# HW2_1.net
KiCad netlist of a schematic drawn in EAGLE
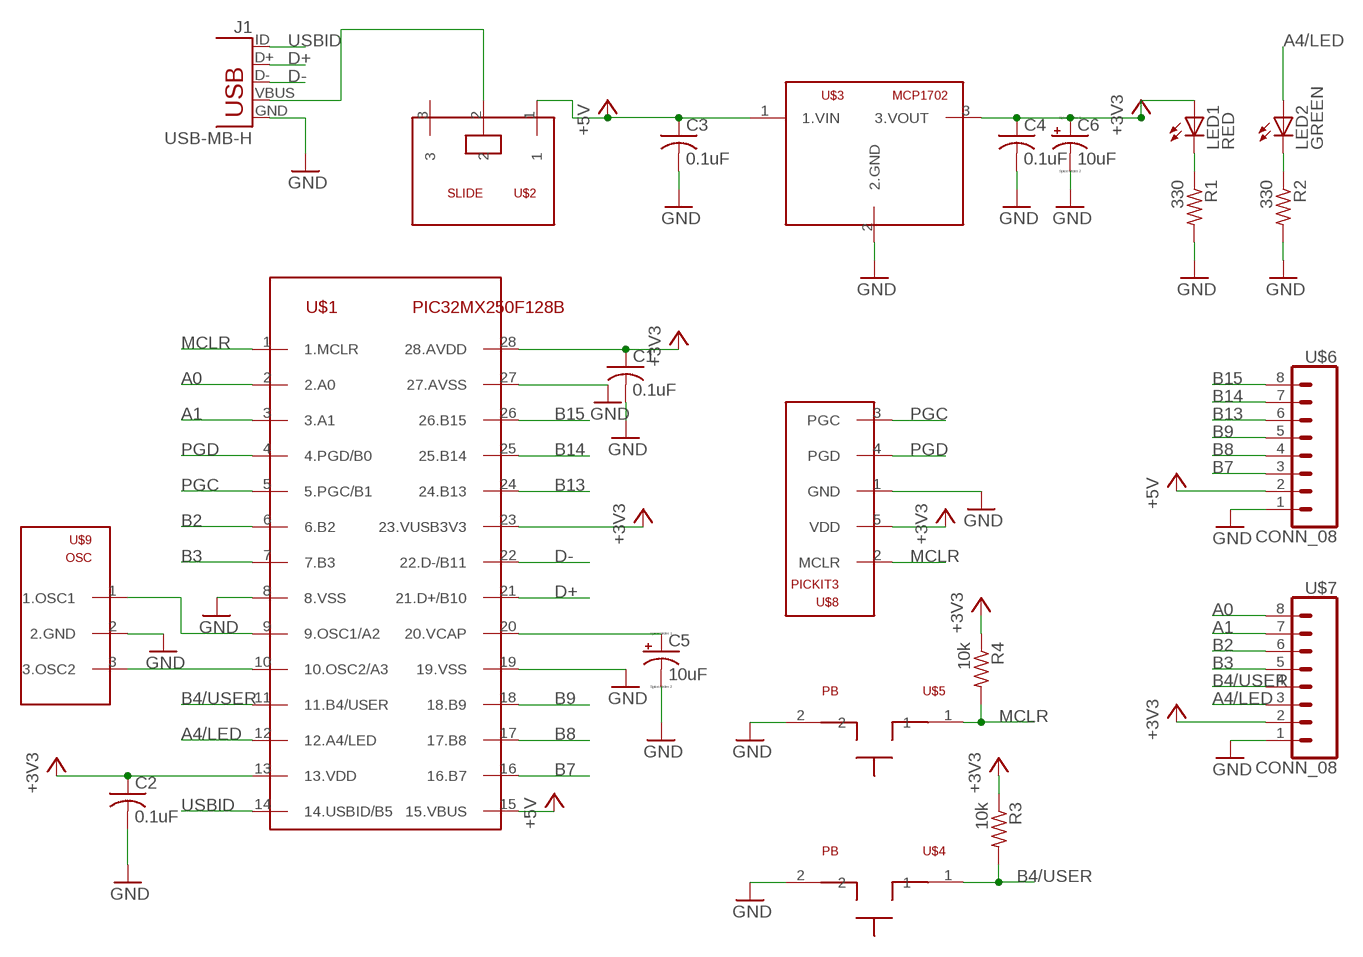
[diagram p0: schematic, sheet 1]

(export (version "E")
  (design (tool "Eeschema 10.0.6"))
  (components
    (comp (ref "C1")
      (value "0.1uF")
      (footprint "eagle-import:C025-025X050")
      (libsource (lib "eagle-import") (part "C-US025-025X050"))
    )
    (comp (ref "C2")
      (value "0.1uF")
      (footprint "eagle-import:C025-025X050")
      (libsource (lib "eagle-import") (part "C-US025-025X050"))
    )
    (comp (ref "C3")
      (value "0.1uF")
      (footprint "eagle-import:C025-025X050")
      (libsource (lib "eagle-import") (part "C-US025-025X050"))
    )
    (comp (ref "C4")
      (value "0.1uF")
      (footprint "eagle-import:C025-025X050")
      (libsource (lib "eagle-import") (part "C-US025-025X050"))
    )
    (comp (ref "C5")
      (value "10uF")
      (footprint "eagle-import:B45181B")
      (libsource (lib "eagle-import") (part "CPOL-USB45181B"))
    )
    (comp (ref "C6")
      (value "10uF")
      (footprint "eagle-import:B45181B")
      (libsource (lib "eagle-import") (part "CPOL-USB45181B"))
    )
    (comp (ref "J1")
      (value "USB-MB-H")
      (footprint "eagle-import:USB-MB-H")
      (libsource (lib "eagle-import") (part "USB-MB-H"))
    )
    (comp (ref "LED1")
      (value "RED")
      (footprint "eagle-import:LED3MM")
      (libsource (lib "eagle-import") (part "LED3MM"))
    )
    (comp (ref "LED2")
      (value "GREEN")
      (footprint "eagle-import:LED3MM")
      (libsource (lib "eagle-import") (part "LED3MM"))
    )
    (comp (ref "R1")
      (value "330")
      (footprint "eagle-import:0207_7")
      (libsource (lib "eagle-import") (part "R-US_0207/7"))
    )
    (comp (ref "R2")
      (value "330")
      (footprint "eagle-import:0207_7")
      (libsource (lib "eagle-import") (part "R-US_0207/7"))
    )
    (comp (ref "R3")
      (value "10k")
      (footprint "eagle-import:0207_7")
      (libsource (lib "eagle-import") (part "R-US_0207/7"))
    )
    (comp (ref "R4")
      (value "10k")
      (footprint "eagle-import:0207_7")
      (libsource (lib "eagle-import") (part "R-US_0207/7"))
    )
    (comp (ref "U$1")
      (value "PIC32MX250F128B")
      (footprint "eagle-import:DIL28-3")
      (libsource (lib "eagle-import") (part "PIC32MX250F128B"))
    )
    (comp (ref "U$2")
      (value "SLIDE")
      (footprint "eagle-import:SLIDE")
      (libsource (lib "eagle-import") (part "SLIDE"))
    )
    (comp (ref "U$3")
      (value "MCP1702")
      (footprint "eagle-import:TO92")
      (libsource (lib "eagle-import") (part "MCP1702"))
    )
    (comp (ref "U$4") (value "PB") (footprint "eagle-import:PB") (libsource (lib "eagle-import") (part "PB")))
    (comp (ref "U$5") (value "PB") (footprint "eagle-import:PB") (libsource (lib "eagle-import") (part "PB")))
    (comp (ref "U$6")
      (value "CONN_08")
      (footprint "eagle-import:1X08")
      (libsource (lib "eagle-import") (part "CONN_08"))
    )
    (comp (ref "U$7")
      (value "CONN_08")
      (footprint "eagle-import:1X08")
      (libsource (lib "eagle-import") (part "CONN_08"))
    )
    (comp (ref "U$8")
      (value "PICKIT3")
      (footprint "eagle-import:1X05")
      (libsource (lib "eagle-import") (part "PICKIT3"))
    )
    (comp (ref "U$9")
      (value "OSC")
      (footprint "eagle-import:OSC")
      (libsource (lib "eagle-import") (part "OSC"))
    )
  )
  (nets
    (net (code "1") (name "+3V3") (class "Default")
      (node (ref "C1") (pin "1") (pinfunction "1_1") (pintype "passive"))
      (node (ref "C2") (pin "1") (pinfunction "1_1") (pintype "passive"))
      (node (ref "C4") (pin "1") (pinfunction "1_1") (pintype "passive"))
      (node (ref "C6") (pin "+") (pinfunction "+_+") (pintype "passive"))
      (node (ref "LED1") (pin "A") (pinfunction "A_A") (pintype "passive"))
      (node (ref "R3") (pin "1") (pinfunction "1_1") (pintype "passive"))
      (node (ref "R4") (pin "1") (pinfunction "1_1") (pintype "passive"))
      (node (ref "U$1") (pin "13") (pinfunction "13.VDD_13") (pintype "bidirectional"))
      (node (ref "U$1") (pin "23") (pinfunction "23.VUSB3V3_23") (pintype "bidirectional"))
      (node (ref "U$1") (pin "28") (pinfunction "28.AVDD_28") (pintype "bidirectional"))
      (node (ref "U$3") (pin "3") (pinfunction "3.VOUT_3") (pintype "bidirectional"))
      (node (ref "U$7") (pin "2") (pinfunction "2_2") (pintype "passive"))
      (node (ref "U$8") (pin "5") (pinfunction "VDD_5") (pintype "bidirectional"))
    )
    (net (code "2") (name "+5V") (class "Default")
      (node (ref "C3") (pin "1") (pinfunction "1_1") (pintype "passive"))
      (node (ref "U$1") (pin "15") (pinfunction "15.VBUS_15") (pintype "bidirectional"))
      (node (ref "U$2") (pin "1") (pinfunction "1_1") (pintype "bidirectional"))
      (node (ref "U$3") (pin "1") (pinfunction "1.VIN_1") (pintype "bidirectional"))
      (node (ref "U$6") (pin "2") (pinfunction "2_2") (pintype "passive"))
    )
    (net (code "3") (name "/A0") (class "Default")
      (node (ref "U$1") (pin "2") (pinfunction "2.A0_2") (pintype "bidirectional"))
      (node (ref "U$7") (pin "8") (pinfunction "8_8") (pintype "passive"))
    )
    (net (code "4") (name "/A1") (class "Default")
      (node (ref "U$1") (pin "3") (pinfunction "3.A1_3") (pintype "bidirectional"))
      (node (ref "U$7") (pin "7") (pinfunction "7_7") (pintype "passive"))
    )
    (net (code "5") (name "/A4{slash}LED") (class "Default")
      (node (ref "LED2") (pin "A") (pinfunction "A_A") (pintype "passive"))
      (node (ref "U$1") (pin "12") (pinfunction "12.A4/LED_12") (pintype "bidirectional"))
      (node (ref "U$7") (pin "3") (pinfunction "3_3") (pintype "passive"))
    )
    (net (code "6") (name "/B2") (class "Default")
      (node (ref "U$1") (pin "6") (pinfunction "6.B2_6") (pintype "bidirectional"))
      (node (ref "U$7") (pin "6") (pinfunction "6_6") (pintype "passive"))
    )
    (net (code "7") (name "/B3") (class "Default")
      (node (ref "U$1") (pin "7") (pinfunction "7.B3_7") (pintype "bidirectional"))
      (node (ref "U$7") (pin "5") (pinfunction "5_5") (pintype "passive"))
    )
    (net (code "8") (name "/B4{slash}USER") (class "Default")
      (node (ref "R3") (pin "2") (pinfunction "2_2") (pintype "passive"))
      (node (ref "U$1") (pin "11") (pinfunction "11.B4/USER_11") (pintype "bidirectional"))
      (node (ref "U$4") (pin "1") (pinfunction "1_1") (pintype "bidirectional"))
      (node (ref "U$7") (pin "4") (pinfunction "4_4") (pintype "passive"))
    )
    (net (code "9") (name "/B7") (class "Default")
      (node (ref "U$1") (pin "16") (pinfunction "16.B7_16") (pintype "bidirectional"))
      (node (ref "U$6") (pin "3") (pinfunction "3_3") (pintype "passive"))
    )
    (net (code "10") (name "/B8") (class "Default")
      (node (ref "U$1") (pin "17") (pinfunction "17.B8_17") (pintype "bidirectional"))
      (node (ref "U$6") (pin "4") (pinfunction "4_4") (pintype "passive"))
    )
    (net (code "11") (name "/B9") (class "Default")
      (node (ref "U$1") (pin "18") (pinfunction "18.B9_18") (pintype "bidirectional"))
      (node (ref "U$6") (pin "5") (pinfunction "5_5") (pintype "passive"))
    )
    (net (code "12") (name "/B13") (class "Default")
      (node (ref "U$1") (pin "24") (pinfunction "24.B13_24") (pintype "bidirectional"))
      (node (ref "U$6") (pin "6") (pinfunction "6_6") (pintype "passive"))
    )
    (net (code "13") (name "/B14") (class "Default")
      (node (ref "U$1") (pin "25") (pinfunction "25.B14_25") (pintype "bidirectional"))
      (node (ref "U$6") (pin "7") (pinfunction "7_7") (pintype "passive"))
    )
    (net (code "14") (name "/B15") (class "Default")
      (node (ref "U$1") (pin "26") (pinfunction "26.B15_26") (pintype "bidirectional"))
      (node (ref "U$6") (pin "8") (pinfunction "8_8") (pintype "passive"))
    )
    (net (code "15") (name "/D+") (class "Default")
      (node (ref "J1") (pin "D+") (pinfunction "D+_D+") (pintype "bidirectional"))
      (node (ref "U$1") (pin "21") (pinfunction "21.D+/B10_21") (pintype "bidirectional"))
    )
    (net (code "16") (name "/D-") (class "Default")
      (node (ref "J1") (pin "D-") (pinfunction "D-_D-") (pintype "bidirectional"))
      (node (ref "U$1") (pin "22") (pinfunction "22.D-/B11_22") (pintype "bidirectional"))
    )
    (net (code "17") (name "/MCLR") (class "Default")
      (node (ref "R4") (pin "2") (pinfunction "2_2") (pintype "passive"))
      (node (ref "U$1") (pin "1") (pinfunction "1.MCLR_1") (pintype "bidirectional"))
      (node (ref "U$5") (pin "1") (pinfunction "1_1") (pintype "bidirectional"))
      (node (ref "U$8") (pin "2") (pinfunction "MCLR_2") (pintype "bidirectional"))
    )
    (net (code "18") (name "/PGC") (class "Default")
      (node (ref "U$1") (pin "5") (pinfunction "5.PGC/B1_5") (pintype "bidirectional"))
      (node (ref "U$8") (pin "3") (pinfunction "PGC_3") (pintype "bidirectional"))
    )
    (net (code "19") (name "/PGD") (class "Default")
      (node (ref "U$1") (pin "4") (pinfunction "4.PGD/B0_4") (pintype "bidirectional"))
      (node (ref "U$8") (pin "4") (pinfunction "PGD_4") (pintype "bidirectional"))
    )
    (net (code "20") (name "/USBID") (class "Default")
      (node (ref "J1") (pin "ID") (pinfunction "ID_ID") (pintype "bidirectional"))
      (node (ref "U$1") (pin "14") (pinfunction "14.USBID/B5_14") (pintype "bidirectional"))
    )
    (net (code "21") (name "GND") (class "Default")
      (node (ref "C1") (pin "2") (pinfunction "2_2") (pintype "passive"))
      (node (ref "C2") (pin "2") (pinfunction "2_2") (pintype "passive"))
      (node (ref "C3") (pin "2") (pinfunction "2_2") (pintype "passive"))
      (node (ref "C4") (pin "2") (pinfunction "2_2") (pintype "passive"))
      (node (ref "C5") (pin "-") (pinfunction "-_-") (pintype "passive"))
      (node (ref "C6") (pin "-") (pinfunction "-_-") (pintype "passive"))
      (node (ref "J1") (pin "GND") (pinfunction "GND_GND") (pintype "bidirectional"))
      (node (ref "R1") (pin "2") (pinfunction "2_2") (pintype "passive"))
      (node (ref "R2") (pin "2") (pinfunction "2_2") (pintype "passive"))
      (node (ref "U$1") (pin "19") (pinfunction "19.VSS_19") (pintype "bidirectional"))
      (node (ref "U$1") (pin "27") (pinfunction "27.AVSS_27") (pintype "bidirectional"))
      (node (ref "U$1") (pin "8") (pinfunction "8.VSS_8") (pintype "bidirectional"))
      (node (ref "U$3") (pin "2") (pinfunction "2.GND_2") (pintype "bidirectional"))
      (node (ref "U$4") (pin "2") (pinfunction "2_2") (pintype "bidirectional"))
      (node (ref "U$5") (pin "2") (pinfunction "2_2") (pintype "bidirectional"))
      (node (ref "U$6") (pin "1") (pinfunction "1_1") (pintype "passive"))
      (node (ref "U$7") (pin "1") (pinfunction "1_1") (pintype "passive"))
      (node (ref "U$8") (pin "1") (pinfunction "GND_1") (pintype "bidirectional"))
      (node (ref "U$9") (pin "2") (pinfunction "2.GND_2") (pintype "bidirectional"))
    )
    (net (code "22") (name "Net-(J1-PadVBUS)") (class "Default")
      (node (ref "J1") (pin "VBUS") (pinfunction "VBUS_VBUS") (pintype "bidirectional"))
      (node (ref "U$2") (pin "2") (pinfunction "2_2") (pintype "bidirectional"))
    )
    (net (code "23") (name "Net-(LED1-C)") (class "Default")
      (node (ref "LED1") (pin "K") (pinfunction "C_K") (pintype "passive"))
      (node (ref "R1") (pin "1") (pinfunction "1_1") (pintype "passive"))
    )
    (net (code "24") (name "Net-(LED2-C)") (class "Default")
      (node (ref "LED2") (pin "K") (pinfunction "C_K") (pintype "passive"))
      (node (ref "R2") (pin "1") (pinfunction "1_1") (pintype "passive"))
    )
    (net (code "25") (name "Net-(U$1-9.OSC1{slash}A2)") (class "Default")
      (node (ref "U$1") (pin "9") (pinfunction "9.OSC1/A2_9") (pintype "bidirectional"))
      (node (ref "U$9") (pin "1") (pinfunction "1.OSC1_1") (pintype "bidirectional"))
    )
    (net (code "26") (name "Net-(U$1-10.OSC2{slash}A3)") (class "Default")
      (node (ref "U$1") (pin "10") (pinfunction "10.OSC2/A3_10") (pintype "bidirectional"))
      (node (ref "U$9") (pin "3") (pinfunction "3.OSC2_3") (pintype "bidirectional"))
    )
    (net (code "27") (name "Net-(U$1-20.VCAP)") (class "Default")
      (node (ref "C5") (pin "+") (pinfunction "+_+") (pintype "passive"))
      (node (ref "U$1") (pin "20") (pinfunction "20.VCAP_20") (pintype "bidirectional"))
    )
    (net (code "28") (name "unconnected-(U$2-Pad3)") (class "Default")
      (node (ref "U$2") (pin "3") (pinfunction "3_3") (pintype "bidirectional"))
    )
  )
)
